# Interboard.net
KiCad netlist of a schematic drawn in Altium Designer
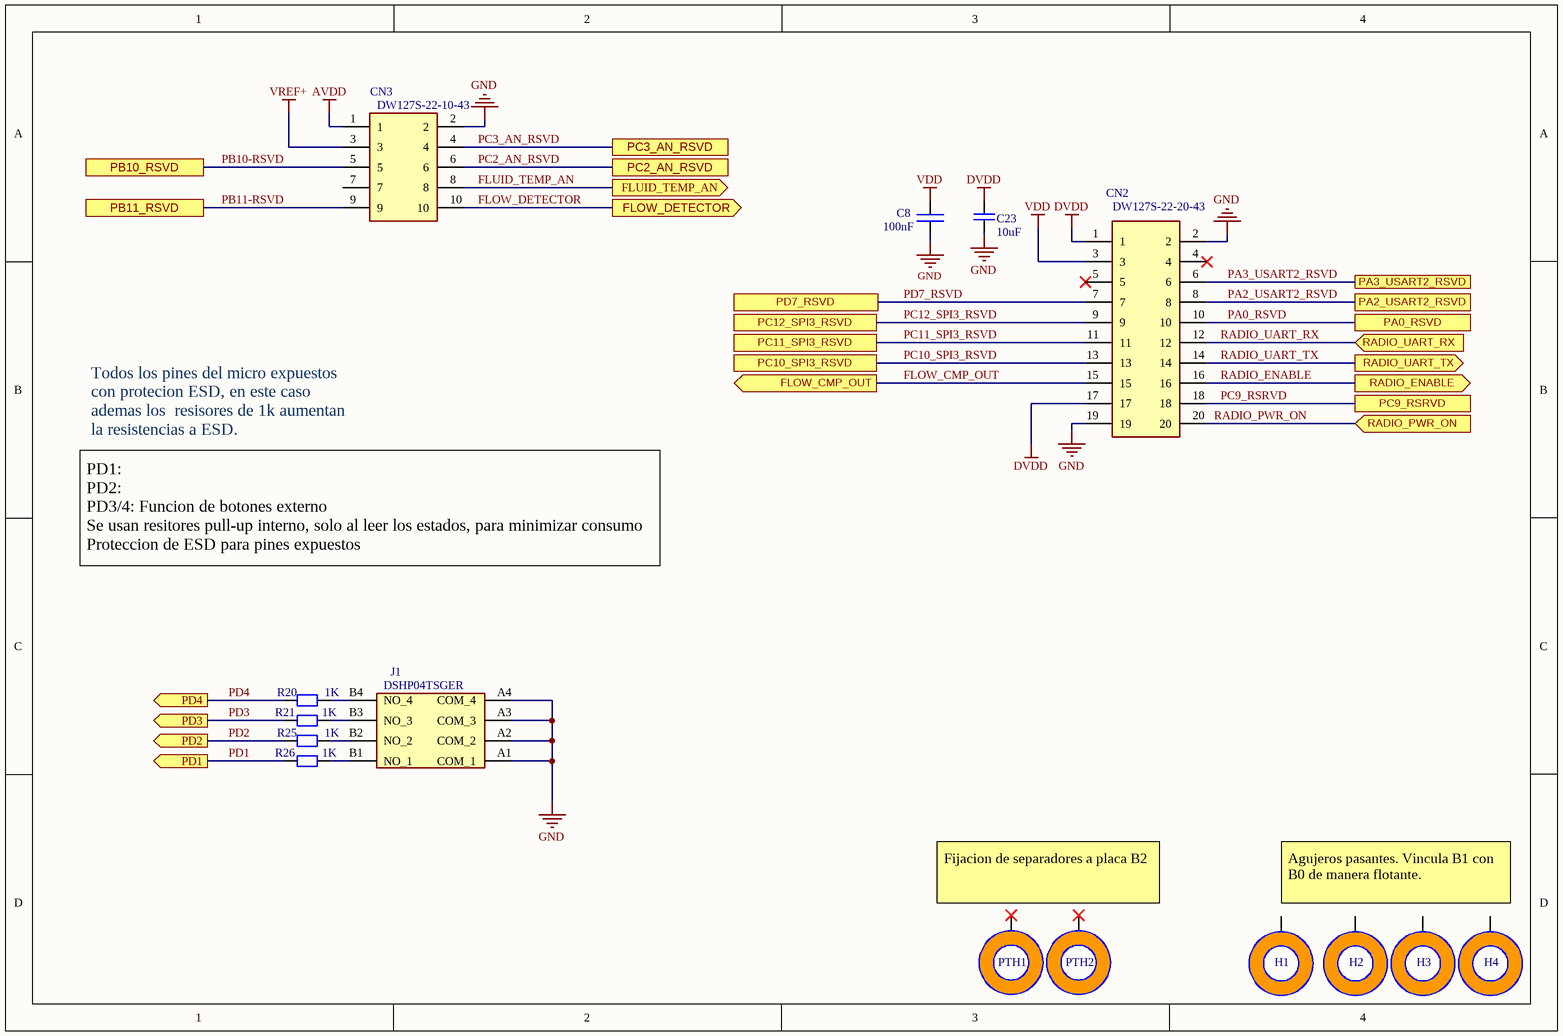
[diagram p0: Interboard.SchDoc]

(export (version "E")
  (design (tool "Eeschema 10.0.6"))
  (components
    (comp (ref "C8")
      (value "100nF")
      (footprint "CAP_SM0603_YAGEOCC2_N")
      (description "CAP 100nF SM0603 X7R 50V YAGEO CC2")
      (fields
        (field (name "MANUFACTURER") "Yageo")
        (field (name "MANUFACTURER PART NUMBER") "CC0603KRX7R9BB104")
      )
      (libsource (lib "yageo") (part "CC0603KRX7R9BB104"))
    )
    (comp (ref "C23")
      (value "10uF")
      (footprint "CAP_SM0603_YAGEOCC2_N")
      (description "CAP 10uF SM0603 X5R 10V YAGEO")
      (fields
        (field (name "MANUFACTURER") "Yageo")
        (field (name "MANUFACTURER PART NUMBER") "CC0603KRX5R6BB106")
      )
      (libsource (lib "yageo") (part "CC0603KRX5R6BB106"))
    )
    (comp (ref "CN2")
      (value "DW127S-22-20-43")
      (footprint "DW127S-22-20-43")
      (description "Header Female SMD 1.27mm 2x10")
      (fields (field (name "MANUFACTURER") "Dealon"))
      (libsource (lib "flowmeet") (part "DW127S-22-20-43"))
    )
    (comp (ref "CN3")
      (value "DW127S-22-10-43")
      (footprint "DW127S-22-10-43")
      (description "Header Female SMD 1.27mm 2x5")
      (fields (field (name "MANUFACTURER") "Dealon"))
      (libsource (lib "flowmeet") (part "DW127S-22-10-43"))
    )
    (comp (ref "H1")
      (value "C193465-HOLE")
      (footprint "C193465-HOLE")
      (description "Agujero pasante")
      (libsource (lib "flowmeet") (part "C193465-HOLE"))
    )
    (comp (ref "H2")
      (value "C193465-HOLE")
      (footprint "C193465-HOLE")
      (description "Agujero pasante")
      (libsource (lib "flowmeet") (part "C193465-HOLE"))
    )
    (comp (ref "H3")
      (value "C193465-HOLE")
      (footprint "C193465-HOLE")
      (description "Agujero pasante")
      (libsource (lib "flowmeet") (part "C193465-HOLE"))
    )
    (comp (ref "H4")
      (value "C193465-HOLE")
      (footprint "C193465-HOLE")
      (description "Agujero pasante")
      (libsource (lib "flowmeet") (part "C193465-HOLE"))
    )
    (comp (ref "J1")
      (value "DSHP04TSGER")
      (footprint "DSHP04TSGER")
      (description "DIP Switches / SIP Switches 4pos 0.025A 24VDC 1/2 Pitch")
      (fields (field (name "MANUFACTURER") "Kangshen") (field (name "VENDOR PART NUMBER") "C3293144"))
      (libsource (lib "flowmeet") (part "DSHP04TSGER"))
    )
    (comp (ref "PTH1")
      (value "PTH-2MM-M")
      (footprint "PTH_M2_M")
      (description "Montaje rosca 2mm, holgura miniama")
      (libsource (lib "flowmeet") (part "PTH-2MM-M"))
    )
    (comp (ref "PTH2")
      (value "PTH-2MM-M")
      (footprint "PTH_M2_M")
      (description "Montaje rosca 2mm, holgura miniama")
      (libsource (lib "flowmeet") (part "PTH-2MM-M"))
    )
    (comp (ref "R20")
      (value "1K")
      (footprint "RES_SM0603_YAGEORC_N")
      (description "RES 1K SM0603 YAGEO RC_L")
      (fields
        (field (name "MANUFACTURER") "Yageo")
        (field (name "MANUFACTURER PART NUMBER") "RC0603FR-071KL")
      )
      (libsource (lib "yageo") (part "RC0603FR-071KL"))
    )
    (comp (ref "R21")
      (value "1K")
      (footprint "RES_SM0603_YAGEORC_N")
      (description "RES 1K SM0603 YAGEO RC_L")
      (fields
        (field (name "MANUFACTURER") "Yageo")
        (field (name "MANUFACTURER PART NUMBER") "RC0603FR-071KL")
      )
      (libsource (lib "yageo") (part "RC0603FR-071KL"))
    )
    (comp (ref "R25")
      (value "1K")
      (footprint "RES_SM0603_YAGEORC_N")
      (description "RES 1K SM0603 YAGEO RC_L")
      (fields
        (field (name "MANUFACTURER") "Yageo")
        (field (name "MANUFACTURER PART NUMBER") "RC0603FR-071KL")
      )
      (libsource (lib "yageo") (part "RC0603FR-071KL"))
    )
    (comp (ref "R26")
      (value "1K")
      (footprint "RES_SM0603_YAGEORC_N")
      (description "RES 1K SM0603 YAGEO RC_L")
      (fields
        (field (name "MANUFACTURER") "Yageo")
        (field (name "MANUFACTURER PART NUMBER") "RC0603FR-071KL")
      )
      (libsource (lib "yageo") (part "RC0603FR-071KL"))
    )
  )
  (nets
    (net (code "1") (name "/FLOW_CMP_OUT") (class "Default")
      (node (ref "CN2") (pin "15") (pinfunction "15_15") (pintype "passive"))
    )
    (net (code "2") (name "/FLOW_DETECTOR") (class "Default")
      (node (ref "CN3") (pin "10") (pinfunction "10_10") (pintype "passive"))
    )
    (net (code "3") (name "/FLUID_TEMP_AN") (class "Default")
      (node (ref "CN3") (pin "8") (pinfunction "8_8") (pintype "passive"))
    )
    (net (code "4") (name "/PA0_RSVD") (class "Default")
      (node (ref "CN2") (pin "10") (pinfunction "10_10") (pintype "passive"))
    )
    (net (code "5") (name "/PA2_USART2_RSVD") (class "Default")
      (node (ref "CN2") (pin "8") (pinfunction "8_8") (pintype "passive"))
    )
    (net (code "6") (name "/PA3_USART2_RSVD") (class "Default")
      (node (ref "CN2") (pin "6") (pinfunction "6_6") (pintype "passive"))
    )
    (net (code "7") (name "/PB10-RSVD") (class "Default")
      (node (ref "CN3") (pin "5") (pinfunction "5_5") (pintype "passive"))
    )
    (net (code "8") (name "/PB11-RSVD") (class "Default")
      (node (ref "CN3") (pin "9") (pinfunction "9_9") (pintype "passive"))
    )
    (net (code "9") (name "/PC2_AN_RSVD") (class "Default")
      (node (ref "CN3") (pin "6") (pinfunction "6_6") (pintype "passive"))
    )
    (net (code "10") (name "/PC3_AN_RSVD") (class "Default")
      (node (ref "CN3") (pin "4") (pinfunction "4_4") (pintype "passive"))
    )
    (net (code "11") (name "/PC9_RSRVD") (class "Default")
      (node (ref "CN2") (pin "18") (pinfunction "18_18") (pintype "passive"))
    )
    (net (code "12") (name "/PC10_SPI3_RSVD") (class "Default")
      (node (ref "CN2") (pin "13") (pinfunction "13_13") (pintype "passive"))
    )
    (net (code "13") (name "/PC11_SPI3_RSVD") (class "Default")
      (node (ref "CN2") (pin "11") (pinfunction "11_11") (pintype "passive"))
    )
    (net (code "14") (name "/PC12_SPI3_RSVD") (class "Default")
      (node (ref "CN2") (pin "9") (pinfunction "9_9") (pintype "passive"))
    )
    (net (code "15") (name "/PD1") (class "Default") (node (ref "R26") (pin "2") (pintype "passive")))
    (net (code "16") (name "/PD2") (class "Default") (node (ref "R25") (pin "2") (pintype "passive")))
    (net (code "17") (name "/PD3") (class "Default") (node (ref "R21") (pin "2") (pintype "passive")))
    (net (code "18") (name "/PD4") (class "Default") (node (ref "R20") (pin "2") (pintype "passive")))
    (net (code "19") (name "/PD7_RSVD") (class "Default")
      (node (ref "CN2") (pin "7") (pinfunction "7_7") (pintype "passive"))
    )
    (net (code "20") (name "/RADIO_ENABLE") (class "Default")
      (node (ref "CN2") (pin "16") (pinfunction "16_16") (pintype "passive"))
    )
    (net (code "21") (name "/RADIO_PWR_ON") (class "Default")
      (node (ref "CN2") (pin "20") (pinfunction "20_20") (pintype "passive"))
    )
    (net (code "22") (name "/RADIO_UART_RX") (class "Default")
      (node (ref "CN2") (pin "12") (pinfunction "12_12") (pintype "passive"))
    )
    (net (code "23") (name "/RADIO_UART_TX") (class "Default")
      (node (ref "CN2") (pin "14") (pinfunction "14_14") (pintype "passive"))
    )
    (net (code "24") (name "AVDD") (class "Default")
      (node (ref "CN3") (pin "1") (pinfunction "1_1") (pintype "passive"))
    )
    (net (code "25") (name "DVDD") (class "Default")
      (node (ref "C23") (pin "1") (pintype "passive"))
      (node (ref "CN2") (pin "1") (pinfunction "1_1") (pintype "passive"))
      (node (ref "CN2") (pin "17") (pinfunction "17_17") (pintype "passive"))
    )
    (net (code "26") (name "GND") (class "Default")
      (node (ref "C23") (pin "2") (pintype "passive"))
      (node (ref "C8") (pin "2") (pintype "passive"))
      (node (ref "CN2") (pin "19") (pinfunction "19_19") (pintype "passive"))
      (node (ref "CN2") (pin "2") (pinfunction "2_2") (pintype "passive"))
      (node (ref "CN3") (pin "2") (pinfunction "2_2") (pintype "passive"))
      (node (ref "J1") (pin "A1") (pinfunction "COM_1_A1") (pintype "passive"))
      (node (ref "J1") (pin "A2") (pinfunction "COM_2_A2") (pintype "passive"))
      (node (ref "J1") (pin "A3") (pinfunction "COM_3_A3") (pintype "passive"))
      (node (ref "J1") (pin "A4") (pinfunction "COM_4_A4") (pintype "passive"))
    )
    (net (code "27") (name "Net-(J1-NO_1)") (class "Default")
      (node (ref "J1") (pin "B1") (pinfunction "NO_1_B1") (pintype "passive"))
      (node (ref "R26") (pin "1") (pintype "passive"))
    )
    (net (code "28") (name "Net-(J1-NO_2)") (class "Default")
      (node (ref "J1") (pin "B2") (pinfunction "NO_2_B2") (pintype "passive"))
      (node (ref "R25") (pin "1") (pintype "passive"))
    )
    (net (code "29") (name "Net-(J1-NO_3)") (class "Default")
      (node (ref "J1") (pin "B3") (pinfunction "NO_3_B3") (pintype "passive"))
      (node (ref "R21") (pin "1") (pintype "passive"))
    )
    (net (code "30") (name "Net-(J1-NO_4)") (class "Default")
      (node (ref "J1") (pin "B4") (pinfunction "NO_4_B4") (pintype "passive"))
      (node (ref "R20") (pin "1") (pintype "passive"))
    )
    (net (code "31") (name "VDD") (class "Default")
      (node (ref "C8") (pin "1") (pintype "passive"))
      (node (ref "CN2") (pin "3") (pinfunction "3_3") (pintype "passive"))
    )
    (net (code "32") (name "VREF+") (class "Default")
      (node (ref "CN3") (pin "3") (pinfunction "3_3") (pintype "passive"))
    )
    (net (code "33") (name "unconnected-(CN2-Pad4)") (class "Default")
      (node (ref "CN2") (pin "4") (pinfunction "4_4") (pintype "passive+no_connect"))
    )
    (net (code "34") (name "unconnected-(CN2-Pad5)") (class "Default")
      (node (ref "CN2") (pin "5") (pinfunction "5_5") (pintype "passive+no_connect"))
    )
    (net (code "35") (name "unconnected-(CN3-Pad7)") (class "Default")
      (node (ref "CN3") (pin "7") (pinfunction "7_7") (pintype "passive"))
    )
    (net (code "36") (name "unconnected-(H1-Pad1)") (class "Default")
      (node (ref "H1") (pin "1") (pinfunction "1_1") (pintype "passive"))
    )
    (net (code "37") (name "unconnected-(H2-Pad1)") (class "Default")
      (node (ref "H2") (pin "1") (pinfunction "1_1") (pintype "passive"))
    )
    (net (code "38") (name "unconnected-(H3-Pad1)") (class "Default")
      (node (ref "H3") (pin "1") (pinfunction "1_1") (pintype "passive"))
    )
    (net (code "39") (name "unconnected-(H4-Pad1)") (class "Default")
      (node (ref "H4") (pin "1") (pinfunction "1_1") (pintype "passive"))
    )
    (net (code "40") (name "unconnected-(PTH1-Pad1)") (class "Default")
      (node (ref "PTH1") (pin "1") (pinfunction "1_1") (pintype "passive+no_connect"))
    )
    (net (code "41") (name "unconnected-(PTH2-Pad1)") (class "Default")
      (node (ref "PTH2") (pin "1") (pinfunction "1_1") (pintype "passive+no_connect"))
    )
  )
)
